# LineReceiver.net
KiCad netlist of a schematic drawn in Altium Designer
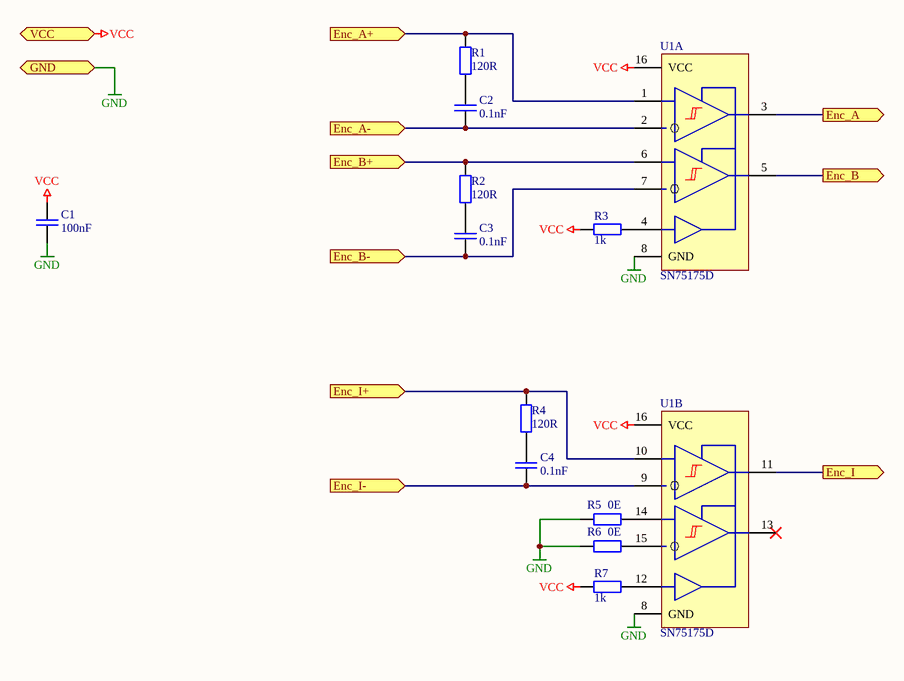
[diagram p0: LineReceiver.SchDoc]

(export (version "E")
  (design (tool "Eeschema 10.0.6"))
  (components
    (comp (ref "C1")
      (value "100nF")
      (footprint "1206")
      (description "Capacitor")
      (fields (field (name "#PUBLISHER") "Dr. A. Heinzelmann"))
      (libsource (lib "mzueger") (part "C"))
    )
    (comp (ref "C2")
      (value "0.1nF")
      (footprint "0805")
      (description "Capacitor")
      (fields (field (name "#PUBLISHER") "Dr. A. Heinzelmann"))
      (libsource (lib "mzueger") (part "C"))
    )
    (comp (ref "C3")
      (value "0.1nF")
      (footprint "0805")
      (description "Capacitor")
      (fields (field (name "#PUBLISHER") "Dr. A. Heinzelmann"))
      (libsource (lib "mzueger") (part "C"))
    )
    (comp (ref "C4")
      (value "0.1nF")
      (footprint "0805")
      (description "Capacitor")
      (fields (field (name "#PUBLISHER") "Dr. A. Heinzelmann"))
      (libsource (lib "mzueger") (part "C"))
    )
    (comp (ref "R1")
      (value "120R")
      (footprint "0805")
      (description "Resistor")
      (fields (field (name "#PUBLISHER") "Dr. A. Heinzelmann"))
      (libsource (lib "mzueger") (part "R"))
    )
    (comp (ref "R2")
      (value "120R")
      (footprint "0805")
      (description "Resistor")
      (fields (field (name "#PUBLISHER") "Dr. A. Heinzelmann"))
      (libsource (lib "mzueger") (part "R"))
    )
    (comp (ref "R3")
      (value "1k")
      (footprint "0805")
      (description "Resistor")
      (fields (field (name "#PUBLISHER") "Dr. A. Heinzelmann"))
      (libsource (lib "") (part "R_1"))
    )
    (comp (ref "R4")
      (value "120R")
      (footprint "0805")
      (description "Resistor")
      (fields (field (name "#PUBLISHER") "Dr. A. Heinzelmann"))
      (libsource (lib "mzueger") (part "R"))
    )
    (comp (ref "R5")
      (value "0E")
      (footprint "0805")
      (description "Resistor")
      (fields (field (name "#PUBLISHER") "Dr. A. Heinzelmann"))
      (libsource (lib "") (part "R_1"))
    )
    (comp (ref "R6")
      (value "0E")
      (footprint "0805")
      (description "Resistor")
      (fields (field (name "#PUBLISHER") "Dr. A. Heinzelmann"))
      (libsource (lib "") (part "R_1"))
    )
    (comp (ref "R7")
      (value "1k")
      (footprint "0805")
      (description "Resistor")
      (fields (field (name "#PUBLISHER") "Dr. A. Heinzelmann"))
      (libsource (lib "") (part "R_1"))
    )
    (comp (ref "U1")
      (value "SN75175D")
      (footprint "SO16-M")
      (description "TEXAS INSTRUMENTS - SN75175D - LINE RECEIVER,QUAD RS485/422/423")
      (fields (field (name "PUBLISHER") "Stefan Ursella, M.Eng"))
      (libsource (lib "mzueger") (part "SN75175D"))
    )
  )
  (nets
    (net (code "1") (name "/Enc_A") (class "Default")
      (node (ref "U1") (pin "3") (pinfunction "3_3") (pintype "passive"))
    )
    (net (code "2") (name "/Enc_A+") (class "Default")
      (node (ref "R1") (pin "2") (pinfunction "2_2") (pintype "passive"))
      (node (ref "U1") (pin "1") (pinfunction "1_1") (pintype "passive"))
    )
    (net (code "3") (name "/Enc_A-") (class "Default")
      (node (ref "C2") (pin "1") (pinfunction "1_1") (pintype "passive"))
      (node (ref "U1") (pin "2") (pinfunction "2_2") (pintype "passive"))
    )
    (net (code "4") (name "/Enc_B") (class "Default")
      (node (ref "U1") (pin "5") (pinfunction "5_5") (pintype "passive"))
    )
    (net (code "5") (name "/Enc_B+") (class "Default")
      (node (ref "R2") (pin "2") (pinfunction "2_2") (pintype "passive"))
      (node (ref "U1") (pin "6") (pinfunction "6_6") (pintype "passive"))
    )
    (net (code "6") (name "/Enc_B-") (class "Default")
      (node (ref "C3") (pin "1") (pinfunction "1_1") (pintype "passive"))
      (node (ref "U1") (pin "7") (pinfunction "7_7") (pintype "passive"))
    )
    (net (code "7") (name "/Enc_I") (class "Default")
      (node (ref "U1") (pin "11") (pinfunction "11_11") (pintype "passive"))
    )
    (net (code "8") (name "/Enc_I+") (class "Default")
      (node (ref "R4") (pin "2") (pinfunction "2_2") (pintype "passive"))
      (node (ref "U1") (pin "10") (pinfunction "10_10") (pintype "passive"))
    )
    (net (code "9") (name "/Enc_I-") (class "Default")
      (node (ref "C4") (pin "1") (pinfunction "1_1") (pintype "passive"))
      (node (ref "U1") (pin "9") (pinfunction "9_9") (pintype "passive"))
    )
    (net (code "10") (name "GND") (class "Default")
      (node (ref "C1") (pin "1") (pinfunction "1_1") (pintype "passive"))
      (node (ref "R5") (pin "2") (pinfunction "2_2") (pintype "passive"))
      (node (ref "R6") (pin "2") (pinfunction "2_2") (pintype "passive"))
      (node (ref "U1") (pin "8") (pinfunction "GND_8") (pintype "passive"))
    )
    (net (code "11") (name "Net-(C2-Pad2)") (class "Default")
      (node (ref "C2") (pin "2") (pinfunction "2_2") (pintype "passive"))
      (node (ref "R1") (pin "1") (pinfunction "1_1") (pintype "passive"))
    )
    (net (code "12") (name "Net-(C3-Pad2)") (class "Default")
      (node (ref "C3") (pin "2") (pinfunction "2_2") (pintype "passive"))
      (node (ref "R2") (pin "1") (pinfunction "1_1") (pintype "passive"))
    )
    (net (code "13") (name "Net-(C4-Pad2)") (class "Default")
      (node (ref "C4") (pin "2") (pinfunction "2_2") (pintype "passive"))
      (node (ref "R4") (pin "1") (pinfunction "1_1") (pintype "passive"))
    )
    (net (code "14") (name "Net-(R5-Pad1)") (class "Default")
      (node (ref "R5") (pin "1") (pinfunction "1_1") (pintype "passive"))
      (node (ref "U1") (pin "14") (pinfunction "14_14") (pintype "passive"))
    )
    (net (code "15") (name "Net-(R6-Pad1)") (class "Default")
      (node (ref "R6") (pin "1") (pinfunction "1_1") (pintype "passive"))
      (node (ref "U1") (pin "15") (pinfunction "15_15") (pintype "passive"))
    )
    (net (code "16") (name "Net-(R7-Pad1)") (class "Default")
      (node (ref "R7") (pin "1") (pinfunction "1_1") (pintype "passive"))
      (node (ref "U1") (pin "12") (pinfunction "12_12") (pintype "passive"))
    )
    (net (code "17") (name "Net-(U1A-EN)") (class "Default")
      (node (ref "R3") (pin "1") (pinfunction "1_1") (pintype "passive"))
      (node (ref "U1") (pin "4") (pinfunction "EN_4") (pintype "passive"))
    )
    (net (code "18") (name "VCC") (class "Default")
      (node (ref "C1") (pin "2") (pinfunction "2_2") (pintype "passive"))
      (node (ref "R3") (pin "2") (pinfunction "2_2") (pintype "passive"))
      (node (ref "R7") (pin "2") (pinfunction "2_2") (pintype "passive"))
      (node (ref "U1") (pin "16") (pinfunction "VCC_16") (pintype "passive"))
    )
    (net (code "19") (name "unconnected-(U1-Pad13)") (class "Default")
      (node (ref "U1") (pin "13") (pinfunction "13_13") (pintype "passive+no_connect"))
    )
  )
)
